# DSO_RAM.net
KiCad netlist of a schematic drawn in Altium Designer
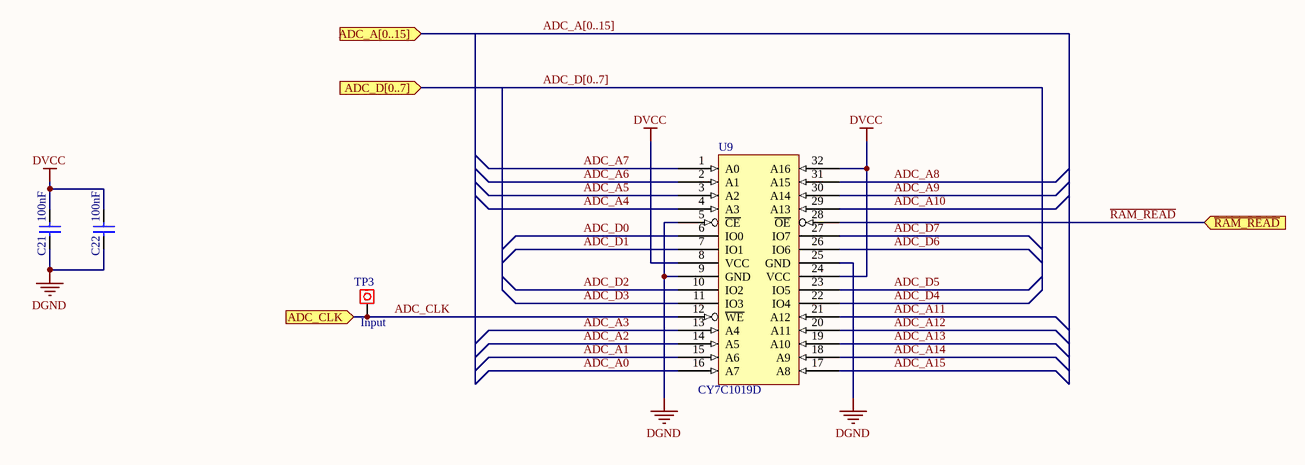
[diagram p0: DSO_RAM.SchDoc]

(export (version "E")
  (design (tool "Eeschema 10.0.6"))
  (components
    (comp (ref "C21")
      (value "100nF")
      (footprint "0805C")
      (description "Capacitor")
      (fields (field (name "REVIEWED BY") "RM - 2018/08/05"))
      (libsource (lib "DSO") (part "C"))
    )
    (comp (ref "C22")
      (value "100nF")
      (footprint "0805C")
      (description "Capacitor")
      (fields (field (name "REVIEWED BY") "RM - 2018/08/05"))
      (libsource (lib "DSO") (part "C"))
    )
    (comp (ref "TP3")
      (value "Input")
      (footprint "Testpoin")
      (description "Pad")
      (fields (field (name "Comment") "INPUT"))
      (libsource (lib "DSO") (part "Test Point"))
    )
    (comp (ref "U9")
      (value "CY7C1019D")
      (footprint "TSOP-32")
      (description "SRAM 128k x 8")
      (fields (field (name "REVIEWED BY") "RM - 2018/08/05"))
      (libsource (lib "DSO") (part "CY7C1019D"))
    )
  )
  (nets
    (net (code "1") (name "/ADC_A0") (class "Default")
      (node (ref "U9") (pin "16") (pinfunction "A7_16") (pintype "input"))
    )
    (net (code "2") (name "/ADC_A1") (class "Default")
      (node (ref "U9") (pin "15") (pinfunction "A6_15") (pintype "input"))
    )
    (net (code "3") (name "/ADC_A2") (class "Default")
      (node (ref "U9") (pin "14") (pinfunction "A5_14") (pintype "input"))
    )
    (net (code "4") (name "/ADC_A3") (class "Default")
      (node (ref "U9") (pin "13") (pinfunction "A4_13") (pintype "input"))
    )
    (net (code "5") (name "/ADC_A4") (class "Default")
      (node (ref "U9") (pin "4") (pinfunction "A3_4") (pintype "input"))
    )
    (net (code "6") (name "/ADC_A5") (class "Default")
      (node (ref "U9") (pin "3") (pinfunction "A2_3") (pintype "input"))
    )
    (net (code "7") (name "/ADC_A6") (class "Default")
      (node (ref "U9") (pin "2") (pinfunction "A1_2") (pintype "input"))
    )
    (net (code "8") (name "/ADC_A7") (class "Default")
      (node (ref "U9") (pin "1") (pinfunction "A0_1") (pintype "input"))
    )
    (net (code "9") (name "/ADC_A8") (class "Default")
      (node (ref "U9") (pin "31") (pinfunction "A15_31") (pintype "input"))
    )
    (net (code "10") (name "/ADC_A9") (class "Default")
      (node (ref "U9") (pin "30") (pinfunction "A14_30") (pintype "input"))
    )
    (net (code "11") (name "/ADC_A10") (class "Default")
      (node (ref "U9") (pin "29") (pinfunction "A13_29") (pintype "input"))
    )
    (net (code "12") (name "/ADC_A11") (class "Default")
      (node (ref "U9") (pin "21") (pinfunction "A12_21") (pintype "input"))
    )
    (net (code "13") (name "/ADC_A12") (class "Default")
      (node (ref "U9") (pin "20") (pinfunction "A11_20") (pintype "input"))
    )
    (net (code "14") (name "/ADC_A13") (class "Default")
      (node (ref "U9") (pin "19") (pinfunction "A10_19") (pintype "input"))
    )
    (net (code "15") (name "/ADC_A14") (class "Default")
      (node (ref "U9") (pin "18") (pinfunction "A9_18") (pintype "input"))
    )
    (net (code "16") (name "/ADC_A15") (class "Default")
      (node (ref "U9") (pin "17") (pinfunction "A8_17") (pintype "input"))
    )
    (net (code "18") (name "/ADC_CLK") (class "Default")
      (node (ref "TP3") (pin "1") (pintype "passive"))
      (node (ref "U9") (pin "12") (pinfunction "~{WE}_12") (pintype "input"))
    )
    (net (code "19") (name "/ADC_D0") (class "Default")
      (node (ref "U9") (pin "6") (pinfunction "IO0_6") (pintype "tri_state"))
    )
    (net (code "20") (name "/ADC_D1") (class "Default")
      (node (ref "U9") (pin "7") (pinfunction "IO1_7") (pintype "tri_state"))
    )
    (net (code "21") (name "/ADC_D2") (class "Default")
      (node (ref "U9") (pin "10") (pinfunction "IO2_10") (pintype "tri_state"))
    )
    (net (code "22") (name "/ADC_D3") (class "Default")
      (node (ref "U9") (pin "11") (pinfunction "IO3_11") (pintype "tri_state"))
    )
    (net (code "23") (name "/ADC_D4") (class "Default")
      (node (ref "U9") (pin "22") (pinfunction "IO4_22") (pintype "tri_state"))
    )
    (net (code "24") (name "/ADC_D5") (class "Default")
      (node (ref "U9") (pin "23") (pinfunction "IO5_23") (pintype "tri_state"))
    )
    (net (code "25") (name "/ADC_D6") (class "Default")
      (node (ref "U9") (pin "26") (pinfunction "IO6_26") (pintype "tri_state"))
    )
    (net (code "26") (name "/ADC_D7") (class "Default")
      (node (ref "U9") (pin "27") (pinfunction "IO7_27") (pintype "tri_state"))
    )
    (net (code "28") (name "/~{RAM_READ}") (class "Default")
      (node (ref "U9") (pin "28") (pinfunction "~{OE}_28") (pintype "input"))
    )
    (net (code "29") (name "DGND") (class "Default")
      (node (ref "C21") (pin "2") (pinfunction "2_2") (pintype "passive"))
      (node (ref "C22") (pin "2") (pinfunction "2_2") (pintype "passive"))
      (node (ref "U9") (pin "25") (pinfunction "GND_25") (pintype "passive"))
      (node (ref "U9") (pin "5") (pinfunction "~{CE}_5") (pintype "input"))
      (node (ref "U9") (pin "9") (pinfunction "GND_9") (pintype "passive"))
    )
    (net (code "30") (name "DVCC") (class "Default")
      (node (ref "C21") (pin "1") (pinfunction "1_1") (pintype "passive"))
      (node (ref "C22") (pin "1") (pinfunction "1_1") (pintype "passive"))
      (node (ref "U9") (pin "24") (pinfunction "VCC_24") (pintype "passive"))
      (node (ref "U9") (pin "32") (pinfunction "A16_32") (pintype "input"))
      (node (ref "U9") (pin "8") (pinfunction "VCC_8") (pintype "passive"))
    )
  )
)
